# HP25E_1.net
KiCad netlist of a schematic drawn in EAGLE
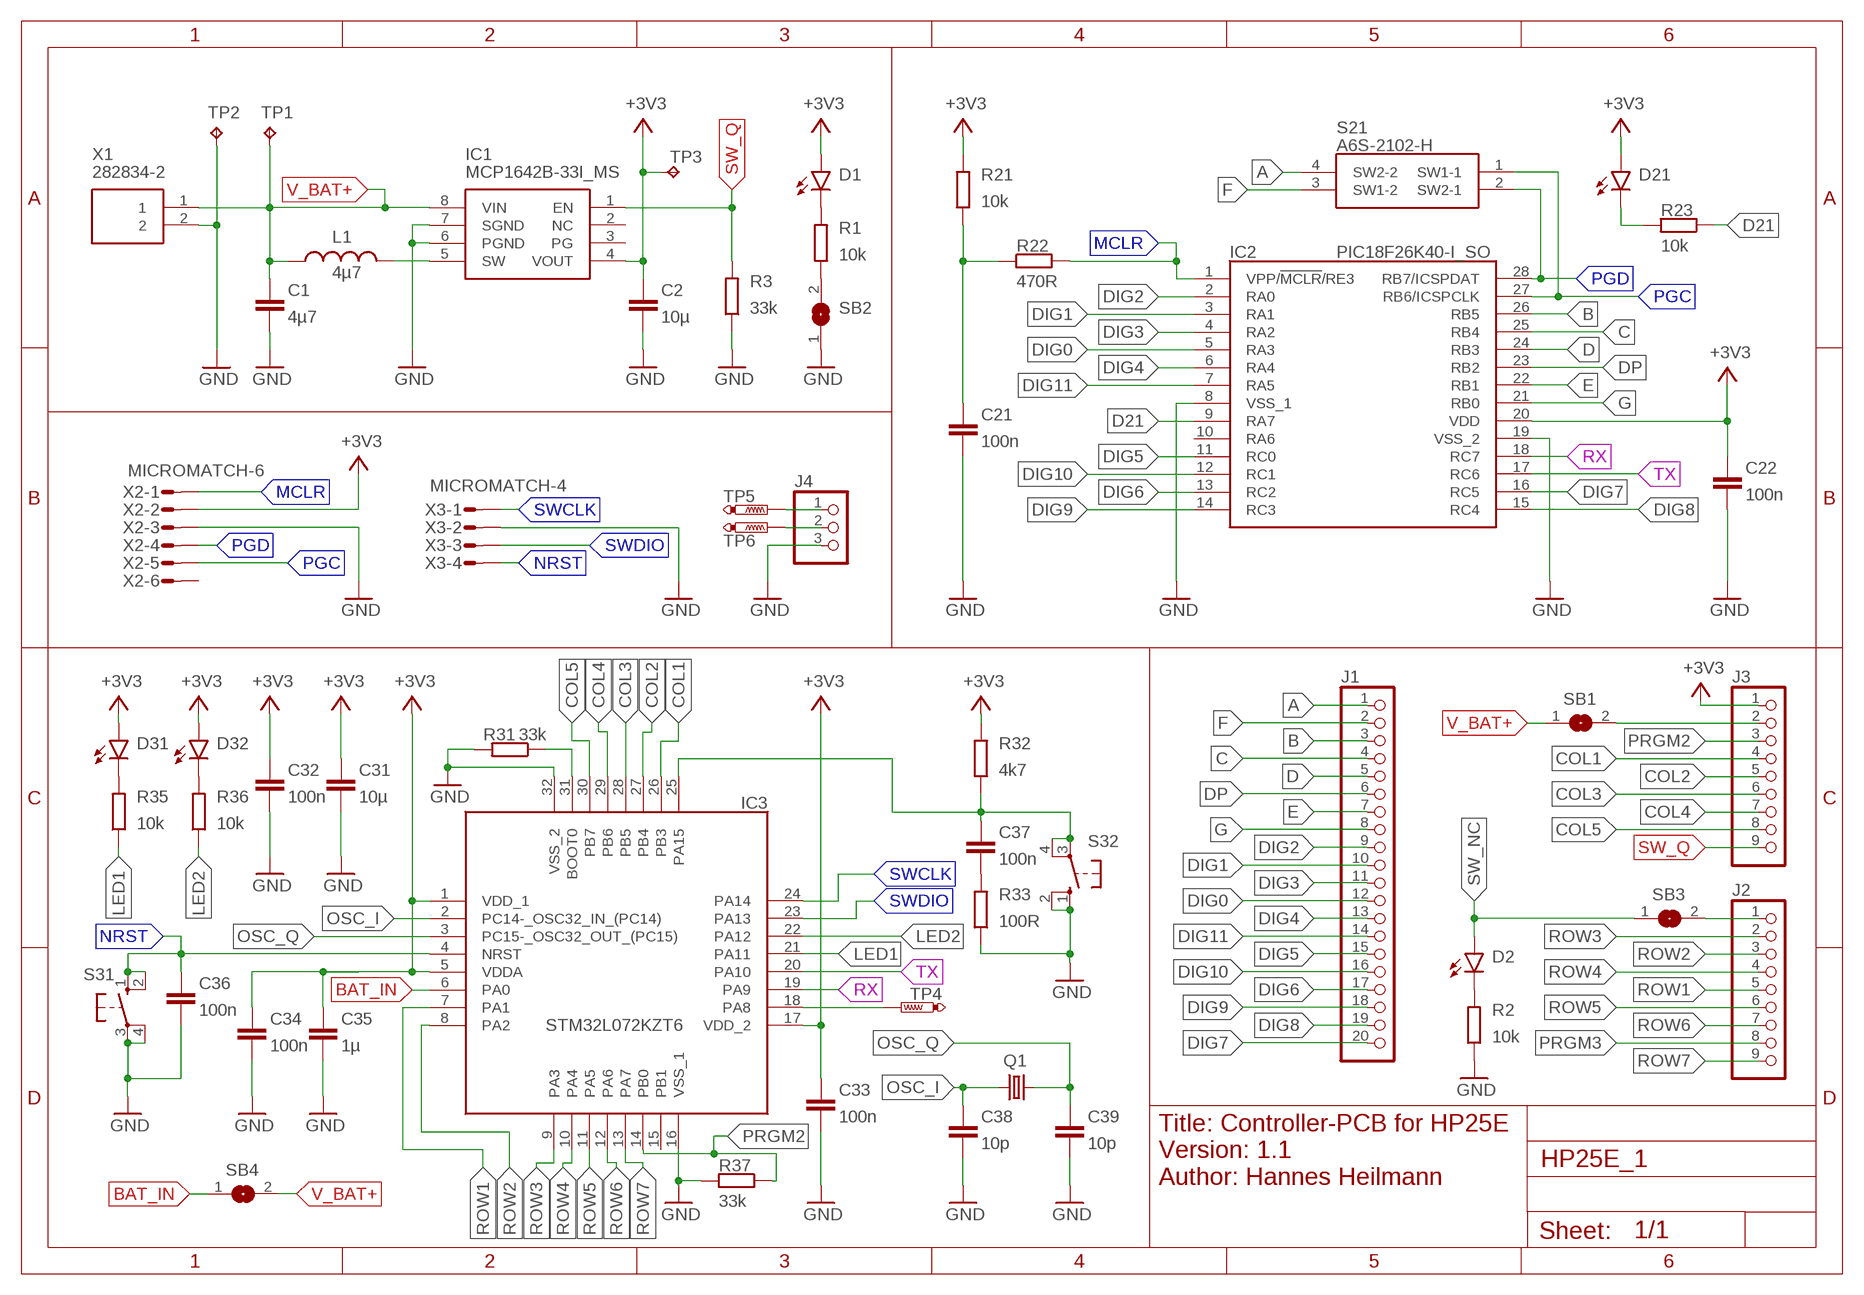
[diagram p0: schematic, sheet 1]

(export (version "E")
  (design (tool "Eeschema 10.0.6"))
  (components
    (comp (ref "C1")
      (value "4µ7")
      (footprint "eagle-import:C1206K")
      (libsource (lib "eagle-import") (part "C-EUC1206K"))
    )
    (comp (ref "C2")
      (value "10µ")
      (footprint "eagle-import:C1206K")
      (libsource (lib "eagle-import") (part "C-EUC1206K"))
    )
    (comp (ref "C21")
      (value "100n")
      (footprint "eagle-import:C0805K")
      (libsource (lib "eagle-import") (part "C-EUC0805K"))
    )
    (comp (ref "C22")
      (value "100n")
      (footprint "eagle-import:C0805K")
      (libsource (lib "eagle-import") (part "C-EUC0805K"))
    )
    (comp (ref "C31")
      (value "10µ")
      (footprint "eagle-import:C1206K")
      (libsource (lib "eagle-import") (part "C-EUC1206K"))
    )
    (comp (ref "C32")
      (value "100n")
      (footprint "eagle-import:C0805K")
      (libsource (lib "eagle-import") (part "C-EUC0805K"))
    )
    (comp (ref "C33")
      (value "100n")
      (footprint "eagle-import:C0805K")
      (libsource (lib "eagle-import") (part "C-EUC0805K"))
    )
    (comp (ref "C34")
      (value "100n")
      (footprint "eagle-import:C0805K")
      (libsource (lib "eagle-import") (part "C-EUC0805K"))
    )
    (comp (ref "C35")
      (value "1µ")
      (footprint "eagle-import:C1206K")
      (libsource (lib "eagle-import") (part "C-EUC1206K"))
    )
    (comp (ref "C36")
      (value "100n")
      (footprint "eagle-import:C0805K")
      (libsource (lib "eagle-import") (part "C-EUC0805K"))
    )
    (comp (ref "C37")
      (value "100n")
      (footprint "eagle-import:C0805K")
      (libsource (lib "eagle-import") (part "C-EUC0805K"))
    )
    (comp (ref "C38")
      (value "10p")
      (footprint "eagle-import:C0805K")
      (libsource (lib "eagle-import") (part "C-EUC0805K"))
    )
    (comp (ref "C39")
      (value "10p")
      (footprint "eagle-import:C0805K")
      (libsource (lib "eagle-import") (part "C-EUC0805K"))
    )
    (comp (ref "D1")
      (value "LEDSML0805")
      (footprint "eagle-import:SML0805")
      (libsource (lib "eagle-import") (part "LEDSML0805"))
    )
    (comp (ref "D2")
      (value "LEDSML0805")
      (footprint "eagle-import:SML0805")
      (libsource (lib "eagle-import") (part "LEDSML0805"))
    )
    (comp (ref "D21")
      (value "LEDSML0805")
      (footprint "eagle-import:SML0805")
      (libsource (lib "eagle-import") (part "LEDSML0805"))
    )
    (comp (ref "D31")
      (value "LEDSML0805")
      (footprint "eagle-import:SML0805")
      (libsource (lib "eagle-import") (part "LEDSML0805"))
    )
    (comp (ref "D32")
      (value "LEDSML0805")
      (footprint "eagle-import:SML0805")
      (libsource (lib "eagle-import") (part "LEDSML0805"))
    )
    (comp (ref "IC1")
      (value "MCP1642B-33I_MS")
      (footprint "eagle-import:SOP65P490X110-8N")
      (fields
        (field (name "ARROW_PART_NUMBER") "MCP1642B-33I/MS")
        (field (name "MOUSER_PART_NUMBER") "579-MCP1642B-33I/MS")
      )
      (libsource (lib "eagle-import") (part "MCP1642B-33I_MS"))
    )
    (comp (ref "IC2")
      (value "PIC18F26K40-I_SO")
      (footprint "eagle-import:SOIC127P1030X265-28N")
      (fields
        (field (name "MANUFACTURER_PART_NUMBER") "PIC18F26K40-I/SO")
        (field (name "MOUSER_PART_NUMBER") "579-PIC18F26K40-I/SO")
        (field (name "RS_PART_NUMBER") "1772185")
      )
      (libsource (lib "eagle-import") (part "PIC18F26K40-I_SO"))
    )
    (comp (ref "IC3")
      (value "STM32L072KZT6")
      (footprint "eagle-import:QFP80P900X900X160-32N")
      (fields (field (name "MOUSER_PART_NUMBER") "511-STM32L072KZT6"))
      (libsource (lib "eagle-import") (part "STM32L072KZT6"))
    )
    (comp (ref "J1")
      (value "PINHD-1X20-BIG")
      (footprint "eagle-import:1X20-BIG")
      (libsource (lib "eagle-import") (part "PINHD-1X20-BIG"))
    )
    (comp (ref "J2")
      (value "PINHD-1X9")
      (footprint "eagle-import:1X09-BIG")
      (libsource (lib "eagle-import") (part "PINHD-1X9"))
    )
    (comp (ref "J3")
      (value "PINHD-1X9")
      (footprint "eagle-import:1X09-BIG")
      (libsource (lib "eagle-import") (part "PINHD-1X9"))
    )
    (comp (ref "J4")
      (value "PINHD-1X3")
      (footprint "eagle-import:1X03")
      (libsource (lib "eagle-import") (part "PINHD-1X3"))
    )
    (comp (ref "L1")
      (value "4µ7")
      (footprint "eagle-import:L4532P")
      (libsource (lib "eagle-import") (part "L-USL4532P"))
    )
    (comp (ref "Q1")
      (value "CRYSTALMM20SS")
      (footprint "eagle-import:MM20SS")
      (libsource (lib "eagle-import") (part "CRYSTALMM20SS"))
    )
    (comp (ref "R1")
      (value "10k")
      (footprint "eagle-import:R0805")
      (libsource (lib "eagle-import") (part "R-EU_R0805"))
    )
    (comp (ref "R2")
      (value "10k")
      (footprint "eagle-import:R0805")
      (libsource (lib "eagle-import") (part "R-EU_R0805"))
    )
    (comp (ref "R3")
      (value "33k")
      (footprint "eagle-import:R0805")
      (libsource (lib "eagle-import") (part "R-EU_R0805"))
    )
    (comp (ref "R21")
      (value "10k")
      (footprint "eagle-import:R0805")
      (libsource (lib "eagle-import") (part "R-EU_R0805"))
    )
    (comp (ref "R22")
      (value "470R")
      (footprint "eagle-import:R0805")
      (libsource (lib "eagle-import") (part "R-EU_R0805"))
    )
    (comp (ref "R23")
      (value "10k")
      (footprint "eagle-import:R0805")
      (libsource (lib "eagle-import") (part "R-EU_R0805"))
    )
    (comp (ref "R31")
      (value "33k")
      (footprint "eagle-import:R0805")
      (libsource (lib "eagle-import") (part "R-EU_R0805"))
    )
    (comp (ref "R32")
      (value "4k7")
      (footprint "eagle-import:R0805")
      (libsource (lib "eagle-import") (part "R-EU_R0805"))
    )
    (comp (ref "R33")
      (value "100R")
      (footprint "eagle-import:R0805")
      (libsource (lib "eagle-import") (part "R-EU_R0805"))
    )
    (comp (ref "R35")
      (value "10k")
      (footprint "eagle-import:R0805")
      (libsource (lib "eagle-import") (part "R-EU_R0805"))
    )
    (comp (ref "R36")
      (value "10k")
      (footprint "eagle-import:R0805")
      (libsource (lib "eagle-import") (part "R-EU_R0805"))
    )
    (comp (ref "R37")
      (value "33k")
      (footprint "eagle-import:R0805")
      (libsource (lib "eagle-import") (part "R-EU_R0805"))
    )
    (comp (ref "S21")
      (value "A6S-2102-H")
      (footprint "eagle-import:SOP254P980X450-4N")
      (fields (field (name "MOUSER_PART_NUMBER") "653-A6S-2102-H") (field (name "RS_PART_NUMBER") "0534768"))
      (libsource (lib "eagle-import") (part "A6S-2102-H"))
    )
    (comp (ref "S31")
      (value "10-XX")
      (footprint "eagle-import:B3F-10XX")
      (fields (field (name "MPN") "B3F-1000"))
      (libsource (lib "eagle-import") (part "10-XX"))
    )
    (comp (ref "S32")
      (value "10-XX")
      (footprint "eagle-import:B3F-10XX")
      (fields (field (name "MPN") "B3F-1000"))
      (libsource (lib "eagle-import") (part "10-XX"))
    )
    (comp (ref "SB1") (value "SJ") (footprint "eagle-import:SJ") (libsource (lib "eagle-import") (part "SJ")))
    (comp (ref "SB2") (value "SJ") (footprint "eagle-import:SJ") (libsource (lib "eagle-import") (part "SJ")))
    (comp (ref "SB3") (value "SJ") (footprint "eagle-import:SJ") (libsource (lib "eagle-import") (part "SJ")))
    (comp (ref "SB4") (value "SJ") (footprint "eagle-import:SJ") (libsource (lib "eagle-import") (part "SJ")))
    (comp (ref "TP1")
      (value "TPB1,27")
      (footprint "eagle-import:B1,27")
      (libsource (lib "eagle-import") (part "TPB1,27"))
    )
    (comp (ref "TP2")
      (value "TPB1,27")
      (footprint "eagle-import:B1,27")
      (libsource (lib "eagle-import") (part "TPB1,27"))
    )
    (comp (ref "TP3")
      (value "TPB1,27")
      (footprint "eagle-import:B1,27")
      (libsource (lib "eagle-import") (part "TPB1,27"))
    )
    (comp (ref "TP4")
      (value "PTR1B1,27")
      (footprint "eagle-import:B1,27")
      (libsource (lib "eagle-import") (part "PTR1B1,27"))
    )
    (comp (ref "TP5")
      (value "PTR1PAD1-13")
      (footprint "eagle-import:P1-13")
      (libsource (lib "eagle-import") (part "PTR1PAD1-13"))
    )
    (comp (ref "TP6")
      (value "PTR1PAD1-13")
      (footprint "eagle-import:P1-13")
      (libsource (lib "eagle-import") (part "PTR1PAD1-13"))
    )
    (comp (ref "X1")
      (value "282834-2")
      (footprint "eagle-import:SHDR2W85P0X254_1X2_554X650X103")
      (libsource (lib "eagle-import") (part "282834-2"))
    )
    (comp (ref "X2")
      (value "MICROMATCH-6")
      (footprint "eagle-import:MICROMATCH-6")
      (fields (field (name "MPN") "7-215464-6"))
      (libsource (lib "eagle-import") (part "MICROMATCH-6"))
    )
    (comp (ref "X3")
      (value "MICROMATCH-4")
      (footprint "eagle-import:MICROMATCH-4")
      (fields (field (name "MPN") "7-215464-4"))
      (libsource (lib "eagle-import") (part "MICROMATCH-4"))
    )
  )
  (nets
    (net (code "1") (name "+3V3") (class "Default")
      (node (ref "C2") (pin "1") (pinfunction "1_1") (pintype "passive"))
      (node (ref "C22") (pin "1") (pinfunction "1_1") (pintype "passive"))
      (node (ref "C31") (pin "1") (pinfunction "1_1") (pintype "passive"))
      (node (ref "C32") (pin "1") (pinfunction "1_1") (pintype "passive"))
      (node (ref "C33") (pin "1") (pinfunction "1_1") (pintype "passive"))
      (node (ref "C34") (pin "1") (pinfunction "1_1") (pintype "passive"))
      (node (ref "C35") (pin "1") (pinfunction "1_1") (pintype "passive"))
      (node (ref "D1") (pin "A") (pinfunction "A_A") (pintype "passive"))
      (node (ref "D21") (pin "A") (pinfunction "A_A") (pintype "passive"))
      (node (ref "D31") (pin "A") (pinfunction "A_A") (pintype "passive"))
      (node (ref "D32") (pin "A") (pinfunction "A_A") (pintype "passive"))
      (node (ref "IC1") (pin "4") (pinfunction "VOUT_4") (pintype "bidirectional"))
      (node (ref "IC2") (pin "20") (pinfunction "VDD_20") (pintype "bidirectional"))
      (node (ref "IC3") (pin "1") (pinfunction "VDD_1_1") (pintype "bidirectional"))
      (node (ref "IC3") (pin "17") (pinfunction "VDD_2_17") (pintype "bidirectional"))
      (node (ref "IC3") (pin "5") (pinfunction "VDDA_5") (pintype "bidirectional"))
      (node (ref "J3") (pin "1") (pinfunction "1_1") (pintype "passive"))
      (node (ref "R21") (pin "2") (pinfunction "2_2") (pintype "passive"))
      (node (ref "R32") (pin "2") (pinfunction "2_2") (pintype "passive"))
      (node (ref "TP3") (pin "TP") (pinfunction "TP_TP") (pintype "input"))
      (node (ref "X2") (pin "2") (pinfunction "S_2") (pintype "passive"))
    )
    (net (code "2") (name "A") (class "Default")
      (node (ref "J1") (pin "1") (pinfunction "1_1") (pintype "passive"))
      (node (ref "S21") (pin "4") (pinfunction "SW2-2_4") (pintype "bidirectional"))
    )
    (net (code "3") (name "B") (class "Default")
      (node (ref "IC2") (pin "26") (pinfunction "RB5_26") (pintype "bidirectional"))
      (node (ref "J1") (pin "3") (pinfunction "3_3") (pintype "passive"))
    )
    (net (code "4") (name "BAT_IN") (class "Default")
      (node (ref "IC3") (pin "6") (pinfunction "PA0_6") (pintype "bidirectional"))
      (node (ref "SB4") (pin "1") (pinfunction "1_1") (pintype "passive"))
    )
    (net (code "5") (name "C") (class "Default")
      (node (ref "IC2") (pin "25") (pinfunction "RB4_25") (pintype "bidirectional"))
      (node (ref "J1") (pin "4") (pinfunction "4_4") (pintype "passive"))
    )
    (net (code "6") (name "COL1") (class "Default")
      (node (ref "IC3") (pin "26") (pinfunction "PB3_26") (pintype "bidirectional"))
      (node (ref "J3") (pin "4") (pinfunction "4_4") (pintype "passive"))
    )
    (net (code "7") (name "COL2") (class "Default")
      (node (ref "IC3") (pin "27") (pinfunction "PB4_27") (pintype "bidirectional"))
      (node (ref "J3") (pin "5") (pinfunction "5_5") (pintype "passive"))
    )
    (net (code "8") (name "COL3") (class "Default")
      (node (ref "IC3") (pin "28") (pinfunction "PB5_28") (pintype "bidirectional"))
      (node (ref "J3") (pin "6") (pinfunction "6_6") (pintype "passive"))
    )
    (net (code "9") (name "COL4") (class "Default")
      (node (ref "IC3") (pin "29") (pinfunction "PB6_29") (pintype "bidirectional"))
      (node (ref "J3") (pin "7") (pinfunction "7_7") (pintype "passive"))
    )
    (net (code "10") (name "COL5") (class "Default")
      (node (ref "IC3") (pin "30") (pinfunction "PB7_30") (pintype "bidirectional"))
      (node (ref "J3") (pin "8") (pinfunction "8_8") (pintype "passive"))
    )
    (net (code "11") (name "D") (class "Default")
      (node (ref "IC2") (pin "24") (pinfunction "RB3_24") (pintype "bidirectional"))
      (node (ref "J1") (pin "5") (pinfunction "5_5") (pintype "passive"))
    )
    (net (code "12") (name "D21") (class "Default")
      (node (ref "IC2") (pin "9") (pinfunction "RA7_9") (pintype "bidirectional"))
      (node (ref "R23") (pin "1") (pinfunction "1_1") (pintype "passive"))
    )
    (net (code "13") (name "DIG0") (class "Default")
      (node (ref "IC2") (pin "5") (pinfunction "RA3_5") (pintype "bidirectional"))
      (node (ref "J1") (pin "12") (pinfunction "12_12") (pintype "passive"))
    )
    (net (code "14") (name "DIG1") (class "Default")
      (node (ref "IC2") (pin "3") (pinfunction "RA1_3") (pintype "bidirectional"))
      (node (ref "J1") (pin "10") (pinfunction "10_10") (pintype "passive"))
    )
    (net (code "15") (name "DIG2") (class "Default")
      (node (ref "IC2") (pin "2") (pinfunction "RA0_2") (pintype "bidirectional"))
      (node (ref "J1") (pin "9") (pinfunction "9_9") (pintype "passive"))
    )
    (net (code "16") (name "DIG3") (class "Default")
      (node (ref "IC2") (pin "4") (pinfunction "RA2_4") (pintype "bidirectional"))
      (node (ref "J1") (pin "11") (pinfunction "11_11") (pintype "passive"))
    )
    (net (code "17") (name "DIG4") (class "Default")
      (node (ref "IC2") (pin "6") (pinfunction "RA4_6") (pintype "bidirectional"))
      (node (ref "J1") (pin "13") (pinfunction "13_13") (pintype "passive"))
    )
    (net (code "18") (name "DIG5") (class "Default")
      (node (ref "IC2") (pin "11") (pinfunction "RC0_11") (pintype "bidirectional"))
      (node (ref "J1") (pin "15") (pinfunction "15_15") (pintype "passive"))
    )
    (net (code "19") (name "DIG6") (class "Default")
      (node (ref "IC2") (pin "13") (pinfunction "RC2_13") (pintype "bidirectional"))
      (node (ref "J1") (pin "17") (pinfunction "17_17") (pintype "passive"))
    )
    (net (code "20") (name "DIG7") (class "Default")
      (node (ref "IC2") (pin "16") (pinfunction "RC5_16") (pintype "bidirectional"))
      (node (ref "J1") (pin "20") (pinfunction "20_20") (pintype "passive"))
    )
    (net (code "21") (name "DIG8") (class "Default")
      (node (ref "IC2") (pin "15") (pinfunction "RC4_15") (pintype "bidirectional"))
      (node (ref "J1") (pin "19") (pinfunction "19_19") (pintype "passive"))
    )
    (net (code "22") (name "DIG9") (class "Default")
      (node (ref "IC2") (pin "14") (pinfunction "RC3_14") (pintype "bidirectional"))
      (node (ref "J1") (pin "18") (pinfunction "18_18") (pintype "passive"))
    )
    (net (code "23") (name "DIG10") (class "Default")
      (node (ref "IC2") (pin "12") (pinfunction "RC1_12") (pintype "bidirectional"))
      (node (ref "J1") (pin "16") (pinfunction "16_16") (pintype "passive"))
    )
    (net (code "24") (name "DIG11") (class "Default")
      (node (ref "IC2") (pin "7") (pinfunction "RA5_7") (pintype "bidirectional"))
      (node (ref "J1") (pin "14") (pinfunction "14_14") (pintype "passive"))
    )
    (net (code "25") (name "DP") (class "Default")
      (node (ref "IC2") (pin "23") (pinfunction "RB2_23") (pintype "bidirectional"))
      (node (ref "J1") (pin "6") (pinfunction "6_6") (pintype "passive"))
    )
    (net (code "26") (name "E") (class "Default")
      (node (ref "IC2") (pin "22") (pinfunction "RB1_22") (pintype "bidirectional"))
      (node (ref "J1") (pin "7") (pinfunction "7_7") (pintype "passive"))
    )
    (net (code "27") (name "F") (class "Default")
      (node (ref "J1") (pin "2") (pinfunction "2_2") (pintype "passive"))
      (node (ref "S21") (pin "3") (pinfunction "SW1-2_3") (pintype "bidirectional"))
    )
    (net (code "28") (name "G") (class "Default")
      (node (ref "IC2") (pin "21") (pinfunction "RB0_21") (pintype "bidirectional"))
      (node (ref "J1") (pin "8") (pinfunction "8_8") (pintype "passive"))
    )
    (net (code "29") (name "GND") (class "Default")
      (node (ref "C1") (pin "2") (pinfunction "2_2") (pintype "passive"))
      (node (ref "C2") (pin "2") (pinfunction "2_2") (pintype "passive"))
      (node (ref "C21") (pin "2") (pinfunction "2_2") (pintype "passive"))
      (node (ref "C22") (pin "2") (pinfunction "2_2") (pintype "passive"))
      (node (ref "C31") (pin "2") (pinfunction "2_2") (pintype "passive"))
      (node (ref "C32") (pin "2") (pinfunction "2_2") (pintype "passive"))
      (node (ref "C33") (pin "2") (pinfunction "2_2") (pintype "passive"))
      (node (ref "C34") (pin "2") (pinfunction "2_2") (pintype "passive"))
      (node (ref "C35") (pin "2") (pinfunction "2_2") (pintype "passive"))
      (node (ref "C36") (pin "2") (pinfunction "2_2") (pintype "passive"))
      (node (ref "C38") (pin "2") (pinfunction "2_2") (pintype "passive"))
      (node (ref "C39") (pin "2") (pinfunction "2_2") (pintype "passive"))
      (node (ref "IC1") (pin "6") (pinfunction "PGND_6") (pintype "bidirectional"))
      (node (ref "IC1") (pin "7") (pinfunction "SGND_7") (pintype "bidirectional"))
      (node (ref "IC2") (pin "19") (pinfunction "VSS_2_19") (pintype "bidirectional"))
      (node (ref "IC2") (pin "8") (pinfunction "VSS_1_8") (pintype "bidirectional"))
      (node (ref "IC3") (pin "16") (pinfunction "VSS_1_16") (pintype "bidirectional"))
      (node (ref "IC3") (pin "32") (pinfunction "VSS_2_32") (pintype "bidirectional"))
      (node (ref "J4") (pin "3") (pinfunction "3_3") (pintype "passive"))
      (node (ref "R2") (pin "1") (pinfunction "1_1") (pintype "passive"))
      (node (ref "R3") (pin "1") (pinfunction "1_1") (pintype "passive"))
      (node (ref "R31") (pin "2") (pinfunction "2_2") (pintype "passive"))
      (node (ref "R33") (pin "1") (pinfunction "1_1") (pintype "passive"))
      (node (ref "R37") (pin "2") (pinfunction "2_2") (pintype "passive"))
      (node (ref "S31") (pin "3") (pinfunction "P_3") (pintype "passive"))
      (node (ref "S31") (pin "4") (pinfunction "P1_4") (pintype "passive"))
      (node (ref "S32") (pin "1") (pinfunction "S_1") (pintype "passive"))
      (node (ref "S32") (pin "2") (pinfunction "S1_2") (pintype "passive"))
      (node (ref "SB2") (pin "1") (pinfunction "1_1") (pintype "passive"))
      (node (ref "TP2") (pin "TP") (pinfunction "TP_TP") (pintype "input"))
      (node (ref "X1") (pin "2") (pinfunction "2_2") (pintype "bidirectional"))
      (node (ref "X2") (pin "3") (pinfunction "S_3") (pintype "passive"))
      (node (ref "X3") (pin "2") (pinfunction "S_2") (pintype "passive"))
    )
    (net (code "30") (name "LED1") (class "Default")
      (node (ref "IC3") (pin "21") (pinfunction "PA11_21") (pintype "bidirectional"))
      (node (ref "R35") (pin "1") (pinfunction "1_1") (pintype "passive"))
    )
    (net (code "31") (name "LED2") (class "Default")
      (node (ref "IC3") (pin "22") (pinfunction "PA12_22") (pintype "bidirectional"))
      (node (ref "R36") (pin "1") (pinfunction "1_1") (pintype "passive"))
    )
    (net (code "32") (name "MCLR") (class "Default")
      (node (ref "IC2") (pin "1") (pinfunction "VPP/~{MCLR}/RE3_1") (pintype "bidirectional"))
      (node (ref "R22") (pin "2") (pinfunction "2_2") (pintype "passive"))
      (node (ref "X2") (pin "1") (pinfunction "S_1") (pintype "passive"))
    )
    (net (code "33") (name "NRST") (class "Default")
      (node (ref "C36") (pin "1") (pinfunction "1_1") (pintype "passive"))
      (node (ref "IC3") (pin "4") (pinfunction "NRST_4") (pintype "bidirectional"))
      (node (ref "S31") (pin "1") (pinfunction "S_1") (pintype "passive"))
      (node (ref "S31") (pin "2") (pinfunction "S1_2") (pintype "passive"))
      (node (ref "X3") (pin "4") (pinfunction "S_4") (pintype "passive"))
    )
    (net (code "34") (name "Net-(C21-Pad1)") (class "Default")
      (node (ref "C21") (pin "1") (pinfunction "1_1") (pintype "passive"))
      (node (ref "R21") (pin "1") (pinfunction "1_1") (pintype "passive"))
      (node (ref "R22") (pin "1") (pinfunction "1_1") (pintype "passive"))
    )
    (net (code "35") (name "Net-(C37-Pad2)") (class "Default")
      (node (ref "C37") (pin "2") (pinfunction "2_2") (pintype "passive"))
      (node (ref "R33") (pin "2") (pinfunction "2_2") (pintype "passive"))
    )
    (net (code "36") (name "Net-(D1-PadC)") (class "Default")
      (node (ref "D1") (pin "C") (pinfunction "C_C") (pintype "passive"))
      (node (ref "R1") (pin "2") (pinfunction "2_2") (pintype "passive"))
    )
    (net (code "37") (name "Net-(D2-PadC)") (class "Default")
      (node (ref "D2") (pin "C") (pinfunction "C_C") (pintype "passive"))
      (node (ref "R2") (pin "2") (pinfunction "2_2") (pintype "passive"))
    )
    (net (code "38") (name "Net-(D21-PadC)") (class "Default")
      (node (ref "D21") (pin "C") (pinfunction "C_C") (pintype "passive"))
      (node (ref "R23") (pin "2") (pinfunction "2_2") (pintype "passive"))
    )
    (net (code "39") (name "Net-(D31-PadC)") (class "Default")
      (node (ref "D31") (pin "C") (pinfunction "C_C") (pintype "passive"))
      (node (ref "R35") (pin "2") (pinfunction "2_2") (pintype "passive"))
    )
    (net (code "40") (name "Net-(D32-PadC)") (class "Default")
      (node (ref "D32") (pin "C") (pinfunction "C_C") (pintype "passive"))
      (node (ref "R36") (pin "2") (pinfunction "2_2") (pintype "passive"))
    )
    (net (code "41") (name "Net-(IC1-SW)") (class "Default")
      (node (ref "IC1") (pin "5") (pinfunction "SW_5") (pintype "bidirectional"))
      (node (ref "L1") (pin "1") (pinfunction "1_1") (pintype "passive"))
    )
    (net (code "42") (name "Net-(IC3-BOOT0)") (class "Default")
      (node (ref "IC3") (pin "31") (pinfunction "BOOT0_31") (pintype "bidirectional"))
      (node (ref "R31") (pin "1") (pinfunction "1_1") (pintype "passive"))
    )
    (net (code "43") (name "Net-(IC3-PA8)") (class "Default")
      (node (ref "IC3") (pin "18") (pinfunction "PA8_18") (pintype "bidirectional"))
      (node (ref "TP4") (pin "TP") (pinfunction "TP_TP") (pintype "input"))
    )
    (net (code "44") (name "Net-(IC3-PA15)") (class "Default")
      (node (ref "C37") (pin "1") (pinfunction "1_1") (pintype "passive"))
      (node (ref "IC3") (pin "25") (pinfunction "PA15_25") (pintype "bidirectional"))
      (node (ref "R32") (pin "1") (pinfunction "1_1") (pintype "passive"))
      (node (ref "S32") (pin "3") (pinfunction "P_3") (pintype "passive"))
      (node (ref "S32") (pin "4") (pinfunction "P1_4") (pintype "passive"))
    )
    (net (code "45") (name "Net-(J2-Pad1)") (class "Default")
      (node (ref "J2") (pin "1") (pinfunction "1_1") (pintype "passive"))
      (node (ref "SB3") (pin "2") (pinfunction "2_2") (pintype "passive"))
    )
    (net (code "46") (name "Net-(J3-Pad2)") (class "Default")
      (node (ref "J3") (pin "2") (pinfunction "2_2") (pintype "passive"))
      (node (ref "SB1") (pin "2") (pinfunction "2_2") (pintype "passive"))
    )
    (net (code "47") (name "Net-(J4-Pad1)") (class "Default")
      (node (ref "J4") (pin "1") (pinfunction "1_1") (pintype "passive"))
      (node (ref "TP5") (pin "TP") (pinfunction "TP_TP") (pintype "input"))
    )
    (net (code "48") (name "Net-(J4-Pad2)") (class "Default")
      (node (ref "J4") (pin "2") (pinfunction "2_2") (pintype "passive"))
      (node (ref "TP6") (pin "TP") (pinfunction "TP_TP") (pintype "input"))
    )
    (net (code "49") (name "Net-(R1-Pad1)") (class "Default")
      (node (ref "R1") (pin "1") (pinfunction "1_1") (pintype "passive"))
      (node (ref "SB2") (pin "2") (pinfunction "2_2") (pintype "passive"))
    )
    (net (code "50") (name "OSC_I") (class "Default")
      (node (ref "C38") (pin "1") (pinfunction "1_1") (pintype "passive"))
      (node (ref "IC3") (pin "2") (pinfunction "PC14-_OSC32_IN_(PC14)_2") (pintype "bidirectional"))
      (node (ref "Q1") (pin "1") (pinfunction "1_1") (pintype "passive"))
    )
    (net (code "51") (name "OSC_Q") (class "Default")
      (node (ref "C39") (pin "1") (pinfunction "1_1") (pintype "passive"))
      (node (ref "IC3") (pin "3") (pinfunction "PC15-_OSC32_OUT_(PC15)_3") (pintype "bidirectional"))
      (node (ref "Q1") (pin "4") (pinfunction "2_4") (pintype "passive"))
    )
    (net (code "52") (name "PGC") (class "Default")
      (node (ref "IC2") (pin "27") (pinfunction "RB6/ICSPCLK_27") (pintype "bidirectional"))
      (node (ref "S21") (pin "1") (pinfunction "SW1-1_1") (pintype "bidirectional"))
      (node (ref "X2") (pin "5") (pinfunction "S_5") (pintype "passive"))
    )
    (net (code "53") (name "PGD") (class "Default")
      (node (ref "IC2") (pin "28") (pinfunction "RB7/ICSPDAT_28") (pintype "bidirectional"))
      (node (ref "S21") (pin "2") (pinfunction "SW2-1_2") (pintype "bidirectional"))
      (node (ref "X2") (pin "4") (pinfunction "S_4") (pintype "passive"))
    )
    (net (code "54") (name "PRGM2") (class "Default")
      (node (ref "IC3") (pin "14") (pinfunction "PB0_14") (pintype "bidirectional"))
      (node (ref "J3") (pin "3") (pinfunction "3_3") (pintype "passive"))
      (node (ref "R37") (pin "1") (pinfunction "1_1") (pintype "passive"))
    )
    (net (code "55") (name "PRGM3") (class "Default")
      (node (ref "J2") (pin "8") (pinfunction "8_8") (pintype "passive"))
    )
    (net (code "56") (name "ROW1") (class "Default")
      (node (ref "IC3") (pin "7") (pinfunction "PA1_7") (pintype "bidirectional"))
      (node (ref "J2") (pin "5") (pinfunction "5_5") (pintype "passive"))
    )
    (net (code "57") (name "ROW2") (class "Default")
      (node (ref "IC3") (pin "8") (pinfunction "PA2_8") (pintype "bidirectional"))
      (node (ref "J2") (pin "3") (pinfunction "3_3") (pintype "passive"))
    )
    (net (code "58") (name "ROW3") (class "Default")
      (node (ref "IC3") (pin "9") (pinfunction "PA3_9") (pintype "bidirectional"))
      (node (ref "J2") (pin "2") (pinfunction "2_2") (pintype "passive"))
    )
    (net (code "59") (name "ROW4") (class "Default")
      (node (ref "IC3") (pin "10") (pinfunction "PA4_10") (pintype "bidirectional"))
      (node (ref "J2") (pin "4") (pinfunction "4_4") (pintype "passive"))
    )
    (net (code "60") (name "ROW5") (class "Default")
      (node (ref "IC3") (pin "11") (pinfunction "PA5_11") (pintype "bidirectional"))
      (node (ref "J2") (pin "6") (pinfunction "6_6") (pintype "passive"))
    )
    (net (code "61") (name "ROW6") (class "Default")
      (node (ref "IC3") (pin "12") (pinfunction "PA6_12") (pintype "bidirectional"))
      (node (ref "J2") (pin "7") (pinfunction "7_7") (pintype "passive"))
    )
    (net (code "62") (name "ROW7") (class "Default")
      (node (ref "IC3") (pin "13") (pinfunction "PA7_13") (pintype "bidirectional"))
      (node (ref "J2") (pin "9") (pinfunction "9_9") (pintype "passive"))
    )
    (net (code "63") (name "RX") (class "Default")
      (node (ref "IC2") (pin "18") (pinfunction "RC7_18") (pintype "bidirectional"))
      (node (ref "IC3") (pin "19") (pinfunction "PA9_19") (pintype "bidirectional"))
    )
    (net (code "64") (name "SWCLK") (class "Default")
      (node (ref "IC3") (pin "24") (pinfunction "PA14_24") (pintype "bidirectional"))
      (node (ref "X3") (pin "1") (pinfunction "S_1") (pintype "passive"))
    )
    (net (code "65") (name "SWDIO") (class "Default")
      (node (ref "IC3") (pin "23") (pinfunction "PA13_23") (pintype "bidirectional"))
      (node (ref "X3") (pin "3") (pinfunction "S_3") (pintype "passive"))
    )
    (net (code "66") (name "SW_NC") (class "Default")
      (node (ref "D2") (pin "A") (pinfunction "A_A") (pintype "passive"))
      (node (ref "SB3") (pin "1") (pinfunction "1_1") (pintype "passive"))
    )
    (net (code "67") (name "SW_Q") (class "Default")
      (node (ref "IC1") (pin "1") (pinfunction "EN_1") (pintype "bidirectional"))
      (node (ref "J3") (pin "9") (pinfunction "9_9") (pintype "passive"))
      (node (ref "R3") (pin "2") (pinfunction "2_2") (pintype "passive"))
    )
    (net (code "68") (name "TX") (class "Default")
      (node (ref "IC2") (pin "17") (pinfunction "RC6_17") (pintype "bidirectional"))
      (node (ref "IC3") (pin "20") (pinfunction "PA10_20") (pintype "bidirectional"))
    )
    (net (code "69") (name "V_BAT+") (class "Default")
      (node (ref "C1") (pin "1") (pinfunction "1_1") (pintype "passive"))
      (node (ref "IC1") (pin "8") (pinfunction "VIN_8") (pintype "bidirectional"))
      (node (ref "L1") (pin "2") (pinfunction "2_2") (pintype "passive"))
      (node (ref "SB1") (pin "1") (pinfunction "1_1") (pintype "passive"))
      (node (ref "SB4") (pin "2") (pinfunction "2_2") (pintype "passive"))
      (node (ref "TP1") (pin "TP") (pinfunction "TP_TP") (pintype "input"))
      (node (ref "X1") (pin "1") (pinfunction "1_1") (pintype "bidirectional"))
    )
    (net (code "70") (name "unconnected-(IC1-NC-Pad2)") (class "Default")
      (node (ref "IC1") (pin "2") (pinfunction "NC_2") (pintype "no_connect"))
    )
    (net (code "71") (name "unconnected-(IC1-PG-Pad3)") (class "Default")
      (node (ref "IC1") (pin "3") (pinfunction "PG_3") (pintype "bidirectional"))
    )
    (net (code "72") (name "unconnected-(IC2-RA6-Pad10)") (class "Default")
      (node (ref "IC2") (pin "10") (pinfunction "RA6_10") (pintype "bidirectional"))
    )
    (net (code "73") (name "unconnected-(IC3-PB1-Pad15)") (class "Default")
      (node (ref "IC3") (pin "15") (pinfunction "PB1_15") (pintype "bidirectional"))
    )
    (net (code "74") (name "unconnected-(X2F-S-Pad6)") (class "Default")
      (node (ref "X2") (pin "6") (pinfunction "S_6") (pintype "passive"))
    )
  )
)
